# Mosfetyxbee.net
KiCad netlist of a schematic drawn in EAGLE
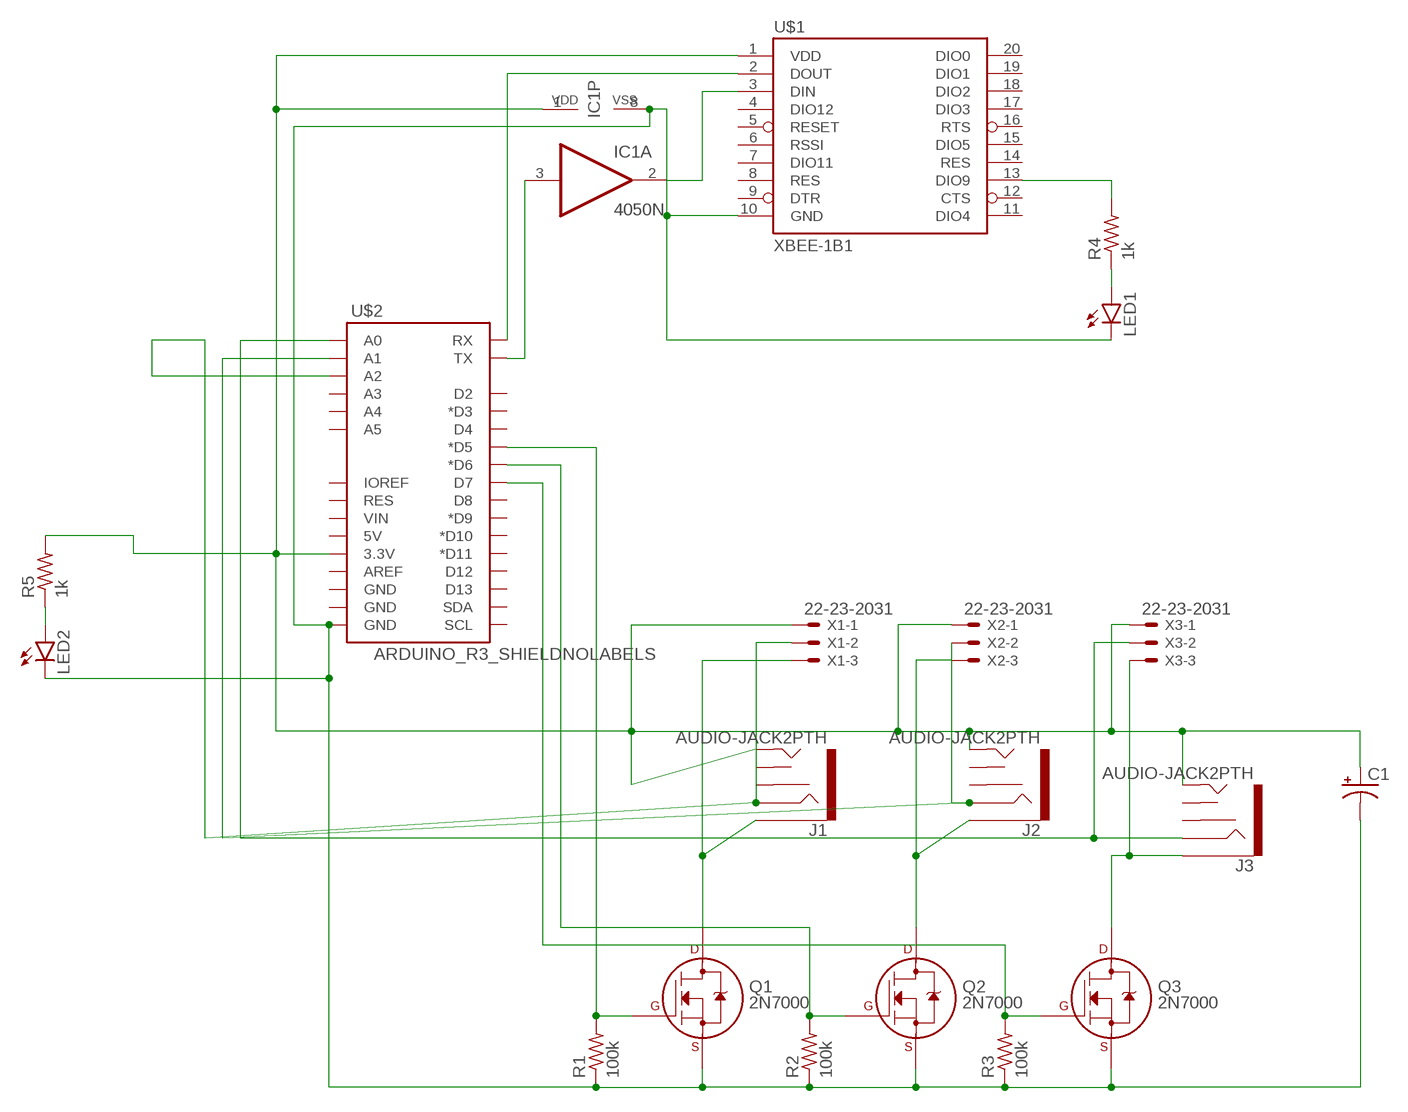
[diagram p0: schematic, sheet 1]

(export (version "E")
  (design (tool "Eeschema 10.0.6"))
  (components
    (comp (ref "C1")
      (value "CAP_POLPTH2")
      (footprint "eagle-import:CPOL-RADIAL-10UF-25V")
      (libsource (lib "eagle-import") (part "CAP_POLPTH2"))
    )
    (comp (ref "IC1")
      (value "4050N")
      (footprint "eagle-import:DIL16")
      (libsource (lib "eagle-import") (part "4050N"))
    )
    (comp (ref "J1")
      (value "AUDIO-JACK2PTH")
      (footprint "eagle-import:AUDIO-JACK")
      (libsource (lib "eagle-import") (part "AUDIO-JACK2PTH"))
    )
    (comp (ref "J2")
      (value "AUDIO-JACK2PTH")
      (footprint "eagle-import:AUDIO-JACK")
      (libsource (lib "eagle-import") (part "AUDIO-JACK2PTH"))
    )
    (comp (ref "J3")
      (value "AUDIO-JACK2PTH")
      (footprint "eagle-import:AUDIO-JACK")
      (libsource (lib "eagle-import") (part "AUDIO-JACK2PTH"))
    )
    (comp (ref "LED1")
      (value "LED3MM")
      (footprint "eagle-import:LED3MM")
      (libsource (lib "eagle-import") (part "LED3MM"))
    )
    (comp (ref "LED2")
      (value "LED3MM")
      (footprint "eagle-import:LED3MM")
      (libsource (lib "eagle-import") (part "LED3MM"))
    )
    (comp (ref "Q1")
      (value "2N7000")
      (footprint "eagle-import:TO-92")
      (libsource (lib "eagle-import") (part "2N700_TO920"))
    )
    (comp (ref "Q2")
      (value "2N7000")
      (footprint "eagle-import:TO-92")
      (libsource (lib "eagle-import") (part "2N700_TO920"))
    )
    (comp (ref "Q3")
      (value "2N7000")
      (footprint "eagle-import:TO-92")
      (libsource (lib "eagle-import") (part "2N700_TO920"))
    )
    (comp (ref "R1")
      (value "100k")
      (footprint "eagle-import:0207_12")
      (libsource (lib "eagle-import") (part "R-US_0207/12"))
    )
    (comp (ref "R2")
      (value "100k")
      (footprint "eagle-import:0207_12")
      (libsource (lib "eagle-import") (part "R-US_0207/12"))
    )
    (comp (ref "R3")
      (value "100k")
      (footprint "eagle-import:0207_12")
      (libsource (lib "eagle-import") (part "R-US_0207/12"))
    )
    (comp (ref "R4")
      (value "1k")
      (footprint "eagle-import:0207_10")
      (libsource (lib "eagle-import") (part "R-US_0207/10"))
    )
    (comp (ref "R5")
      (value "1k")
      (footprint "eagle-import:0207_10")
      (libsource (lib "eagle-import") (part "R-US_0207/10"))
    )
    (comp (ref "U$1")
      (value "XBEE-1B1")
      (footprint "eagle-import:XBEE-1")
      (libsource (lib "eagle-import") (part "XBEE-1B1"))
    )
    (comp (ref "U$2")
      (value "ARDUINO_R3_SHIELDNOLABELS")
      (footprint "eagle-import:UNO_R3_SHIELD_NOLABELS")
      (libsource (lib "eagle-import") (part "ARDUINO_R3_SHIELDNOLABELS"))
    )
    (comp (ref "X1")
      (value "22-23-2031")
      (footprint "eagle-import:22-23-2031")
      (fields (field (name "MF") "MOLEX"))
      (libsource (lib "eagle-import") (part "22-23-2031"))
    )
    (comp (ref "X2")
      (value "22-23-2031")
      (footprint "eagle-import:22-23-2031")
      (fields (field (name "MF") "MOLEX"))
      (libsource (lib "eagle-import") (part "22-23-2031"))
    )
    (comp (ref "X3")
      (value "22-23-2031")
      (footprint "eagle-import:22-23-2031")
      (fields (field (name "MF") "MOLEX"))
      (libsource (lib "eagle-import") (part "22-23-2031"))
    )
  )
  (nets
    (net (code "1") (name "Net-(C1-+)") (class "Default")
      (node (ref "C1") (pin "1") (pinfunction "+_1") (pintype "passive"))
      (node (ref "IC1") (pin "1") (pinfunction "VDD_1") (pintype "power_in"))
      (node (ref "J1") (pin "TIP") (pinfunction "TIP_TIP") (pintype "bidirectional"))
      (node (ref "J2") (pin "TIP") (pinfunction "TIP_TIP") (pintype "bidirectional"))
      (node (ref "J3") (pin "TIP") (pinfunction "TIP_TIP") (pintype "bidirectional"))
      (node (ref "R5") (pin "2") (pinfunction "2_2") (pintype "passive"))
      (node (ref "U$1") (pin "1") (pinfunction "VDD_1") (pintype "power_in"))
      (node (ref "U$2") (pin "3.3V") (pinfunction "3.3V_3.3V") (pintype "bidirectional"))
      (node (ref "X1") (pin "1") (pinfunction "S_1") (pintype "passive"))
      (node (ref "X2") (pin "1") (pinfunction "S_1") (pintype "passive"))
      (node (ref "X3") (pin "1") (pinfunction "S_1") (pintype "passive"))
    )
    (net (code "2") (name "Net-(C1--)") (class "Default")
      (node (ref "C1") (pin "2") (pinfunction "-_2") (pintype "passive"))
      (node (ref "IC1") (pin "8") (pinfunction "VSS_8") (pintype "power_in"))
      (node (ref "LED1") (pin "K") (pinfunction "C_K") (pintype "passive"))
      (node (ref "LED2") (pin "K") (pinfunction "C_K") (pintype "passive"))
      (node (ref "Q1") (pin "1") (pinfunction "S_1") (pintype "bidirectional"))
      (node (ref "Q2") (pin "1") (pinfunction "S_1") (pintype "bidirectional"))
      (node (ref "Q3") (pin "1") (pinfunction "S_1") (pintype "bidirectional"))
      (node (ref "R1") (pin "1") (pinfunction "1_1") (pintype "passive"))
      (node (ref "R2") (pin "1") (pinfunction "1_1") (pintype "passive"))
      (node (ref "R3") (pin "1") (pinfunction "1_1") (pintype "passive"))
      (node (ref "U$1") (pin "10") (pinfunction "GND_10") (pintype "power_in"))
      (node (ref "U$2") (pin "GND@0") (pinfunction "GND_GND@0") (pintype "bidirectional"))
    )
    (net (code "3") (name "Net-(IC1A-I)") (class "Default")
      (node (ref "IC1") (pin "3") (pinfunction "I_3") (pintype "input"))
      (node (ref "U$2") (pin "TX") (pinfunction "TX_TX") (pintype "bidirectional"))
    )
    (net (code "4") (name "Net-(IC1A-O)") (class "Default")
      (node (ref "IC1") (pin "2") (pinfunction "O_2") (pintype "output"))
      (node (ref "U$1") (pin "3") (pinfunction "DIN_3") (pintype "input"))
    )
    (net (code "5") (name "Net-(LED1-PadA)") (class "Default")
      (node (ref "LED1") (pin "A") (pinfunction "A_A") (pintype "passive"))
      (node (ref "R4") (pin "1") (pinfunction "1_1") (pintype "passive"))
    )
    (net (code "6") (name "Net-(LED2-PadA)") (class "Default")
      (node (ref "LED2") (pin "A") (pinfunction "A_A") (pintype "passive"))
      (node (ref "R5") (pin "1") (pinfunction "1_1") (pintype "passive"))
    )
    (net (code "7") (name "Net-(Q1-D)") (class "Default")
      (node (ref "J1") (pin "SLEEVE") (pinfunction "SLEEVE_SLEEVE") (pintype "bidirectional"))
      (node (ref "Q1") (pin "3") (pinfunction "D_3") (pintype "bidirectional"))
      (node (ref "X1") (pin "3") (pinfunction "S_3") (pintype "passive"))
    )
    (net (code "8") (name "Net-(Q1-G)") (class "Default")
      (node (ref "Q1") (pin "2") (pinfunction "G_2") (pintype "tri_state"))
      (node (ref "R1") (pin "2") (pinfunction "2_2") (pintype "passive"))
      (node (ref "U$2") (pin "D5") (pinfunction "*D5_D5") (pintype "bidirectional"))
    )
    (net (code "9") (name "Net-(Q2-D)") (class "Default")
      (node (ref "J2") (pin "SLEEVE") (pinfunction "SLEEVE_SLEEVE") (pintype "bidirectional"))
      (node (ref "Q2") (pin "3") (pinfunction "D_3") (pintype "bidirectional"))
      (node (ref "X2") (pin "3") (pinfunction "S_3") (pintype "passive"))
    )
    (net (code "10") (name "Net-(Q2-G)") (class "Default")
      (node (ref "Q2") (pin "2") (pinfunction "G_2") (pintype "tri_state"))
      (node (ref "R2") (pin "2") (pinfunction "2_2") (pintype "passive"))
      (node (ref "U$2") (pin "D6") (pinfunction "*D6_D6") (pintype "bidirectional"))
    )
    (net (code "11") (name "Net-(Q3-D)") (class "Default")
      (node (ref "J3") (pin "SLEEVE") (pinfunction "SLEEVE_SLEEVE") (pintype "bidirectional"))
      (node (ref "Q3") (pin "3") (pinfunction "D_3") (pintype "bidirectional"))
      (node (ref "X3") (pin "3") (pinfunction "S_3") (pintype "passive"))
    )
    (net (code "12") (name "Net-(Q3-G)") (class "Default")
      (node (ref "Q3") (pin "2") (pinfunction "G_2") (pintype "tri_state"))
      (node (ref "R3") (pin "2") (pinfunction "2_2") (pintype "passive"))
      (node (ref "U$2") (pin "D7") (pinfunction "D7_D7") (pintype "bidirectional"))
    )
    (net (code "13") (name "Net-(U$1-DIO9)") (class "Default")
      (node (ref "R4") (pin "2") (pinfunction "2_2") (pintype "passive"))
      (node (ref "U$1") (pin "13") (pinfunction "DIO9_13") (pintype "bidirectional"))
    )
    (net (code "14") (name "Net-(U$1-DOUT)") (class "Default")
      (node (ref "U$1") (pin "2") (pinfunction "DOUT_2") (pintype "output"))
      (node (ref "U$2") (pin "RX") (pinfunction "RX_RX") (pintype "bidirectional"))
    )
    (net (code "15") (name "Net-(X1B-S)") (class "Default")
      (node (ref "J1") (pin "RING") (pinfunction "RING_RING") (pintype "bidirectional"))
      (node (ref "U$2") (pin "A2") (pinfunction "A2_A2") (pintype "bidirectional"))
      (node (ref "X1") (pin "2") (pinfunction "S_2") (pintype "passive"))
    )
    (net (code "16") (name "Net-(X2B-S)") (class "Default")
      (node (ref "J2") (pin "RING") (pinfunction "RING_RING") (pintype "bidirectional"))
      (node (ref "U$2") (pin "A1") (pinfunction "A1_A1") (pintype "bidirectional"))
      (node (ref "X2") (pin "2") (pinfunction "S_2") (pintype "passive"))
    )
    (net (code "17") (name "Net-(X3B-S)") (class "Default")
      (node (ref "J3") (pin "RING") (pinfunction "RING_RING") (pintype "bidirectional"))
      (node (ref "U$2") (pin "A0") (pinfunction "A0_A0") (pintype "bidirectional"))
      (node (ref "X3") (pin "2") (pinfunction "S_2") (pintype "passive"))
    )
    (net (code "18") (name "unconnected-(J1-PadRSH)") (class "Default")
      (node (ref "J1") (pin "RSH") (pinfunction "RSH_RSH") (pintype "bidirectional"))
    )
    (net (code "19") (name "unconnected-(J1-PadTSH)") (class "Default")
      (node (ref "J1") (pin "TSH") (pinfunction "TSH_TSH") (pintype "bidirectional"))
    )
    (net (code "20") (name "unconnected-(J2-PadRSH)") (class "Default")
      (node (ref "J2") (pin "RSH") (pinfunction "RSH_RSH") (pintype "bidirectional"))
    )
    (net (code "21") (name "unconnected-(J2-PadTSH)") (class "Default")
      (node (ref "J2") (pin "TSH") (pinfunction "TSH_TSH") (pintype "bidirectional"))
    )
    (net (code "22") (name "unconnected-(J3-PadRSH)") (class "Default")
      (node (ref "J3") (pin "RSH") (pinfunction "RSH_RSH") (pintype "bidirectional"))
    )
    (net (code "23") (name "unconnected-(J3-PadTSH)") (class "Default")
      (node (ref "J3") (pin "TSH") (pinfunction "TSH_TSH") (pintype "bidirectional"))
    )
    (net (code "24") (name "unconnected-(U$1-CTS-Pad12)") (class "Default")
      (node (ref "U$1") (pin "12") (pinfunction "CTS_12") (pintype "output"))
    )
    (net (code "25") (name "unconnected-(U$1-DIO0-Pad20)") (class "Default")
      (node (ref "U$1") (pin "20") (pinfunction "DIO0_20") (pintype "bidirectional"))
    )
    (net (code "26") (name "unconnected-(U$1-DIO1-Pad19)") (class "Default")
      (node (ref "U$1") (pin "19") (pinfunction "DIO1_19") (pintype "bidirectional"))
    )
    (net (code "27") (name "unconnected-(U$1-DIO2-Pad18)") (class "Default")
      (node (ref "U$1") (pin "18") (pinfunction "DIO2_18") (pintype "bidirectional"))
    )
    (net (code "28") (name "unconnected-(U$1-DIO3-Pad17)") (class "Default")
      (node (ref "U$1") (pin "17") (pinfunction "DIO3_17") (pintype "bidirectional"))
    )
    (net (code "29") (name "unconnected-(U$1-DIO4-Pad11)") (class "Default")
      (node (ref "U$1") (pin "11") (pinfunction "DIO4_11") (pintype "bidirectional"))
    )
    (net (code "30") (name "unconnected-(U$1-DIO5-Pad15)") (class "Default")
      (node (ref "U$1") (pin "15") (pinfunction "DIO5_15") (pintype "bidirectional"))
    )
    (net (code "31") (name "unconnected-(U$1-DIO11-Pad7)") (class "Default")
      (node (ref "U$1") (pin "7") (pinfunction "DIO11_7") (pintype "bidirectional"))
    )
    (net (code "32") (name "unconnected-(U$1-DIO12-Pad4)") (class "Default")
      (node (ref "U$1") (pin "4") (pinfunction "DIO12_4") (pintype "bidirectional"))
    )
    (net (code "33") (name "unconnected-(U$1-DTR-Pad9)") (class "Default")
      (node (ref "U$1") (pin "9") (pinfunction "DTR_9") (pintype "bidirectional"))
    )
    (net (code "34") (name "unconnected-(U$1-RES-Pad8)") (class "Default")
      (node (ref "U$1") (pin "8") (pinfunction "RES_8") (pintype "bidirectional"))
    )
    (net (code "35") (name "unconnected-(U$1-RES-Pad14)") (class "Default")
      (node (ref "U$1") (pin "14") (pinfunction "RES_14") (pintype "bidirectional"))
    )
    (net (code "36") (name "unconnected-(U$1-RESET-Pad5)") (class "Default")
      (node (ref "U$1") (pin "5") (pinfunction "RESET_5") (pintype "input"))
    )
    (net (code "37") (name "unconnected-(U$1-RSSI-Pad6)") (class "Default")
      (node (ref "U$1") (pin "6") (pinfunction "RSSI_6") (pintype "bidirectional"))
    )
    (net (code "38") (name "unconnected-(U$1-RTS-Pad16)") (class "Default")
      (node (ref "U$1") (pin "16") (pinfunction "RTS_16") (pintype "input"))
    )
    (net (code "39") (name "unconnected-(U$2-*D3-PadD3)") (class "Default")
      (node (ref "U$2") (pin "D3") (pinfunction "*D3_D3") (pintype "bidirectional"))
    )
    (net (code "40") (name "unconnected-(U$2-*D9-PadD9)") (class "Default")
      (node (ref "U$2") (pin "D9") (pinfunction "*D9_D9") (pintype "bidirectional"))
    )
    (net (code "41") (name "unconnected-(U$2-*D10-PadD10)") (class "Default")
      (node (ref "U$2") (pin "D10") (pinfunction "*D10_D10") (pintype "bidirectional"))
    )
    (net (code "42") (name "unconnected-(U$2-*D11-PadD11)") (class "Default")
      (node (ref "U$2") (pin "D11") (pinfunction "*D11_D11") (pintype "bidirectional"))
    )
    (net (code "43") (name "unconnected-(U$2-GND-PadGND@1)") (class "Default")
      (node (ref "U$2") (pin "GND@1") (pinfunction "GND_GND@1") (pintype "bidirectional"))
    )
    (net (code "44") (name "unconnected-(U$2-GND-PadGND@2)") (class "Default")
      (node (ref "U$2") (pin "GND@2") (pinfunction "GND_GND@2") (pintype "bidirectional"))
    )
    (net (code "45") (name "unconnected-(U$2-Pad5V)") (class "Default")
      (node (ref "U$2") (pin "5V") (pinfunction "5V_5V") (pintype "bidirectional"))
    )
    (net (code "46") (name "unconnected-(U$2-PadA3)") (class "Default")
      (node (ref "U$2") (pin "A3") (pinfunction "A3_A3") (pintype "bidirectional"))
    )
    (net (code "47") (name "unconnected-(U$2-PadA4)") (class "Default")
      (node (ref "U$2") (pin "A4") (pinfunction "A4_A4") (pintype "bidirectional"))
    )
    (net (code "48") (name "unconnected-(U$2-PadA5)") (class "Default")
      (node (ref "U$2") (pin "A5") (pinfunction "A5_A5") (pintype "bidirectional"))
    )
    (net (code "49") (name "unconnected-(U$2-PadAREF)") (class "Default")
      (node (ref "U$2") (pin "AREF") (pinfunction "AREF_AREF") (pintype "bidirectional"))
    )
    (net (code "50") (name "unconnected-(U$2-PadD2)") (class "Default")
      (node (ref "U$2") (pin "D2") (pinfunction "D2_D2") (pintype "bidirectional"))
    )
    (net (code "51") (name "unconnected-(U$2-PadD4)") (class "Default")
      (node (ref "U$2") (pin "D4") (pinfunction "D4_D4") (pintype "bidirectional"))
    )
    (net (code "52") (name "unconnected-(U$2-PadD8)") (class "Default")
      (node (ref "U$2") (pin "D8") (pinfunction "D8_D8") (pintype "bidirectional"))
    )
    (net (code "53") (name "unconnected-(U$2-PadD12)") (class "Default")
      (node (ref "U$2") (pin "D12") (pinfunction "D12_D12") (pintype "bidirectional"))
    )
    (net (code "54") (name "unconnected-(U$2-PadD13)") (class "Default")
      (node (ref "U$2") (pin "D13") (pinfunction "D13_D13") (pintype "bidirectional"))
    )
    (net (code "55") (name "unconnected-(U$2-PadIOREF)") (class "Default")
      (node (ref "U$2") (pin "IOREF") (pinfunction "IOREF_IOREF") (pintype "bidirectional"))
    )
    (net (code "56") (name "unconnected-(U$2-PadRES)") (class "Default")
      (node (ref "U$2") (pin "RES") (pinfunction "RES_RES") (pintype "bidirectional"))
    )
    (net (code "57") (name "unconnected-(U$2-PadSCL)") (class "Default")
      (node (ref "U$2") (pin "SCL") (pinfunction "SCL_SCL") (pintype "bidirectional"))
    )
    (net (code "58") (name "unconnected-(U$2-PadSDA)") (class "Default")
      (node (ref "U$2") (pin "SDA") (pinfunction "SDA_SDA") (pintype "bidirectional"))
    )
    (net (code "59") (name "unconnected-(U$2-PadVIN)") (class "Default")
      (node (ref "U$2") (pin "VIN") (pinfunction "VIN_VIN") (pintype "bidirectional"))
    )
  )
)
